# 1_MCU.net
KiCad netlist of a schematic drawn in Altium Designer
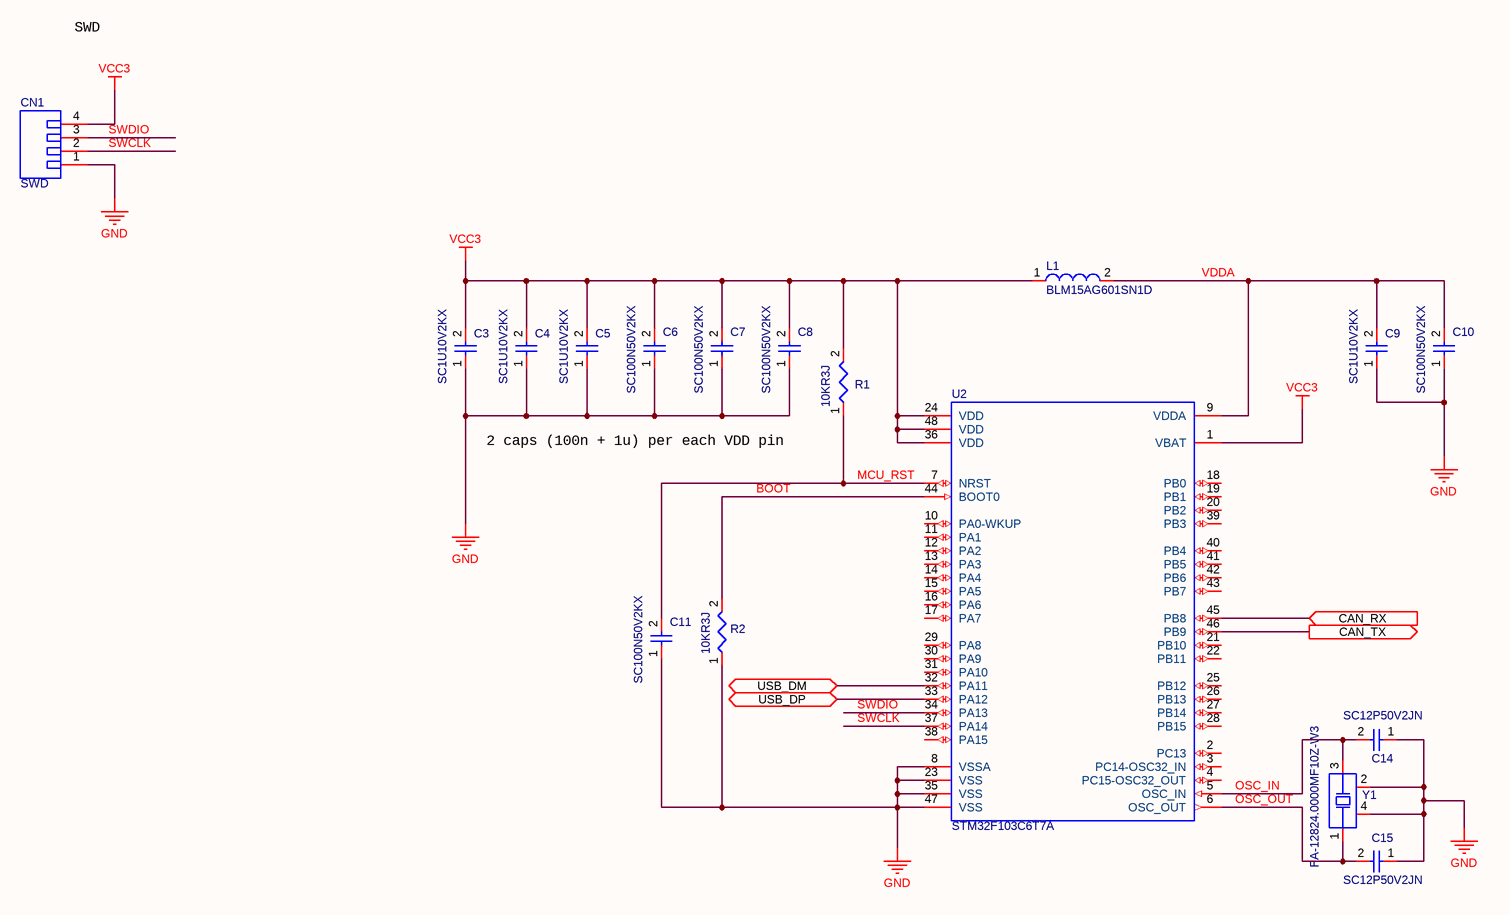
[diagram p0: 1_MCU.SchDoc]

(export (version "E")
  (design (tool "Eeschema 10.0.6"))
  (components
    (comp (ref "C3")
      (value "SC1U10V2KX")
      (footprint "CAPC0402(1005)60_L")
      (description "CAP 1uF 10V ±10% 0402 (1005 Metric) Thickness 0.6mm SMD")
      (libsource (lib "PUMAlib") (part "CAP(0402)1UF10V"))
    )
    (comp (ref "C4")
      (value "SC1U10V2KX")
      (footprint "CAPC0402(1005)60_L")
      (description "CAP 1uF 10V ±10% 0402 (1005 Metric) Thickness 0.6mm SMD")
      (libsource (lib "PUMAlib") (part "CAP(0402)1UF10V"))
    )
    (comp (ref "C5")
      (value "SC1U10V2KX")
      (footprint "CAPC0402(1005)60_L")
      (description "CAP 1uF 10V ±10% 0402 (1005 Metric) Thickness 0.6mm SMD")
      (libsource (lib "PUMAlib") (part "CAP(0402)1UF10V"))
    )
    (comp (ref "C6")
      (value "SC100N50V2KX")
      (footprint "CAPC0402(1005)60_L")
      (description "CAP 100nF 50V ±10% 0402 (1005 Metric) Thickness 0.6mm SMD")
      (libsource (lib "PUMAlib") (part "CAP(0402)100nF50V"))
    )
    (comp (ref "C7")
      (value "SC100N50V2KX")
      (footprint "CAPC0402(1005)60_L")
      (description "CAP 100nF 50V ±10% 0402 (1005 Metric) Thickness 0.6mm SMD")
      (libsource (lib "PUMAlib") (part "CAP(0402)100nF50V"))
    )
    (comp (ref "C8")
      (value "SC100N50V2KX")
      (footprint "CAPC0402(1005)60_L")
      (description "CAP 100nF 50V ±10% 0402 (1005 Metric) Thickness 0.6mm SMD")
      (libsource (lib "PUMAlib") (part "CAP(0402)100nF50V"))
    )
    (comp (ref "C9")
      (value "SC1U10V2KX")
      (footprint "CAPC0402(1005)60_L")
      (description "CAP 1uF 10V ±10% 0402 (1005 Metric) Thickness 0.6mm SMD")
      (libsource (lib "PUMAlib") (part "CAP(0402)1UF10V"))
    )
    (comp (ref "C10")
      (value "SC100N50V2KX")
      (footprint "CAPC0402(1005)60_L")
      (description "CAP 100nF 50V ±10% 0402 (1005 Metric) Thickness 0.6mm SMD")
      (libsource (lib "PUMAlib") (part "CAP(0402)100nF50V"))
    )
    (comp (ref "C11")
      (value "SC100N50V2KX")
      (footprint "CAPC0402(1005)60_L")
      (description "CAP 100nF 50V ±10% 0402 (1005 Metric) Thickness 0.6mm SMD")
      (libsource (lib "PUMAlib") (part "CAP(0402)100nF50V"))
    )
    (comp (ref "C14")
      (value "SC12P50V2JN")
      (footprint "CAPC0402(1005)33_L")
      (description "CAP 12pF 50V ±5% 0402 (1005 Metric) Thickness 0.33mm SMD")
      (libsource (lib "PUMAlib") (part "CAP12pF"))
    )
    (comp (ref "C15")
      (value "SC12P50V2JN")
      (footprint "CAPC0402(1005)33_L")
      (description "CAP 12pF 50V ±5% 0402 (1005 Metric) Thickness 0.33mm SMD")
      (libsource (lib "PUMAlib") (part "CAP12pF"))
    )
    (comp (ref "CN1")
      (value "SWD")
      (footprint "4PHEADERS-2D54")
      (description "4 holes for 18awg wire")
      (fields (field (name "MANUFACTURER") "JST"))
      (libsource (lib "PUMAlib") (part "4PIN-CN"))
    )
    (comp (ref "L1")
      (value "BLM15AG601SN1D")
      (footprint "INDC1005X06L")
      (description "Chip Ferrite Bead Single Type 600 Ohms 300mA")
      (libsource (lib "PUMAlib") (part "IND-filt"))
    )
    (comp (ref "R1")
      (value "10KR3J")
      (footprint "RESC0603(1608)_L")
      (description "10K 0.1W 5% 0603 (1608 Metric)  SMD")
      (libsource (lib "PUMAlib") (part "RES0(0603)_10K"))
    )
    (comp (ref "R2")
      (value "10KR3J")
      (footprint "RESC0603(1608)_L")
      (description "10K 0.1W 5% 0603 (1608 Metric)  SMD")
      (libsource (lib "PUMAlib") (part "RES0(0603)_10K"))
    )
    (comp (ref "U2")
      (value "STM32F103C6T7A")
      (footprint "TSQFP50P900X900X160-48L")
      (description "ARM® Cortex®-M3 STM32F1 Microcontroller IC 32-Bit 72MHz 32KB 48-LFQP (7x7)")
      (libsource (lib "PUMAlib") (part "STM32F103C6T7A"))
    )
    (comp (ref "Y1")
      (value "FA-12824.0000MF10Z-W3")
      (footprint "QRTZ-12mhz")
      (description "Crystal, 24 MHz, +/- 10 ppm, -20 to 75 degC, 4-Pin SMD, RoHS, Tape and Reel")
      (fields (field (name "TOLERANCE") "10ppm"))
      (libsource (lib "PUMAlib") (part "XTAL-1-3-4"))
    )
  )
  (nets
    (net (code "1") (name "/BOOT") (class "Default")
      (node (ref "R2") (pin "2") (pinfunction "2_2") (pintype "passive"))
      (node (ref "U2") (pin "44") (pinfunction "BOOT0_44") (pintype "input"))
    )
    (net (code "2") (name "/CAN_RX") (class "Default")
      (node (ref "U2") (pin "45") (pinfunction "PB8_45") (pintype "bidirectional"))
    )
    (net (code "3") (name "/CAN_TX") (class "Default")
      (node (ref "U2") (pin "46") (pinfunction "PB9_46") (pintype "bidirectional"))
    )
    (net (code "4") (name "/MCU_RST") (class "Default")
      (node (ref "C11") (pin "2") (pinfunction "2_2") (pintype "passive"))
      (node (ref "R1") (pin "1") (pinfunction "1_1") (pintype "passive"))
      (node (ref "U2") (pin "7") (pinfunction "NRST_7") (pintype "bidirectional"))
    )
    (net (code "5") (name "/OSC_IN") (class "Default")
      (node (ref "C14") (pin "2") (pinfunction "2_2") (pintype "passive"))
      (node (ref "U2") (pin "5") (pinfunction "OSC_IN_5") (pintype "input"))
      (node (ref "Y1") (pin "3") (pinfunction "X2_3") (pintype "passive"))
    )
    (net (code "6") (name "/OSC_OUT") (class "Default")
      (node (ref "C15") (pin "2") (pinfunction "2_2") (pintype "passive"))
      (node (ref "U2") (pin "6") (pinfunction "OSC_OUT_6") (pintype "output"))
      (node (ref "Y1") (pin "1") (pinfunction "X1_1") (pintype "passive"))
    )
    (net (code "7") (name "/SWCLK") (class "Default")
      (node (ref "CN1") (pin "2") (pinfunction "2_2") (pintype "passive"))
      (node (ref "U2") (pin "37") (pinfunction "PA14_37") (pintype "bidirectional"))
    )
    (net (code "8") (name "/SWDIO") (class "Default")
      (node (ref "CN1") (pin "3") (pinfunction "3_3") (pintype "passive"))
      (node (ref "U2") (pin "34") (pinfunction "PA13_34") (pintype "bidirectional"))
    )
    (net (code "9") (name "/USB_DM") (class "Default")
      (node (ref "U2") (pin "32") (pinfunction "PA11_32") (pintype "bidirectional"))
    )
    (net (code "10") (name "/USB_DP") (class "Default")
      (node (ref "U2") (pin "33") (pinfunction "PA12_33") (pintype "bidirectional"))
    )
    (net (code "11") (name "/VDDA") (class "Default")
      (node (ref "C10") (pin "2") (pinfunction "2_2") (pintype "passive"))
      (node (ref "C9") (pin "2") (pinfunction "2_2") (pintype "passive"))
      (node (ref "L1") (pin "2") (pinfunction "2_2") (pintype "passive"))
      (node (ref "U2") (pin "9") (pinfunction "VDDA_9") (pintype "power_in"))
    )
    (net (code "12") (name "GND") (class "Default")
      (node (ref "C10") (pin "1") (pinfunction "1_1") (pintype "passive"))
      (node (ref "C11") (pin "1") (pinfunction "1_1") (pintype "passive"))
      (node (ref "C14") (pin "1") (pinfunction "1_1") (pintype "passive"))
      (node (ref "C15") (pin "1") (pinfunction "1_1") (pintype "passive"))
      (node (ref "C3") (pin "1") (pinfunction "1_1") (pintype "passive"))
      (node (ref "C4") (pin "1") (pinfunction "1_1") (pintype "passive"))
      (node (ref "C5") (pin "1") (pinfunction "1_1") (pintype "passive"))
      (node (ref "C6") (pin "1") (pinfunction "1_1") (pintype "passive"))
      (node (ref "C7") (pin "1") (pinfunction "1_1") (pintype "passive"))
      (node (ref "C8") (pin "1") (pinfunction "1_1") (pintype "passive"))
      (node (ref "C9") (pin "1") (pinfunction "1_1") (pintype "passive"))
      (node (ref "CN1") (pin "1") (pinfunction "1_1") (pintype "passive"))
      (node (ref "R2") (pin "1") (pinfunction "1_1") (pintype "passive"))
      (node (ref "U2") (pin "23") (pinfunction "VSS_23") (pintype "power_in"))
      (node (ref "U2") (pin "35") (pinfunction "VSS_35") (pintype "power_in"))
      (node (ref "U2") (pin "47") (pinfunction "VSS_47") (pintype "power_in"))
      (node (ref "U2") (pin "8") (pinfunction "VSSA_8") (pintype "power_in"))
      (node (ref "Y1") (pin "2") (pinfunction "NC_2") (pintype "power_in"))
      (node (ref "Y1") (pin "4") (pinfunction "NC_4") (pintype "power_in"))
    )
    (net (code "13") (name "VCC3") (class "Default")
      (node (ref "C3") (pin "2") (pinfunction "2_2") (pintype "passive"))
      (node (ref "C4") (pin "2") (pinfunction "2_2") (pintype "passive"))
      (node (ref "C5") (pin "2") (pinfunction "2_2") (pintype "passive"))
      (node (ref "C6") (pin "2") (pinfunction "2_2") (pintype "passive"))
      (node (ref "C7") (pin "2") (pinfunction "2_2") (pintype "passive"))
      (node (ref "C8") (pin "2") (pinfunction "2_2") (pintype "passive"))
      (node (ref "CN1") (pin "4") (pinfunction "4_4") (pintype "passive"))
      (node (ref "L1") (pin "1") (pinfunction "1_1") (pintype "passive"))
      (node (ref "R1") (pin "2") (pinfunction "2_2") (pintype "passive"))
      (node (ref "U2") (pin "1") (pinfunction "VBAT_1") (pintype "power_in"))
      (node (ref "U2") (pin "24") (pinfunction "VDD_24") (pintype "power_in"))
      (node (ref "U2") (pin "36") (pinfunction "VDD_36") (pintype "power_in"))
      (node (ref "U2") (pin "48") (pinfunction "VDD_48") (pintype "power_in"))
    )
    (net (code "14") (name "unconnected-(U2-PA0-WKUP-Pad10)") (class "Default")
      (node (ref "U2") (pin "10") (pinfunction "PA0-WKUP_10") (pintype "bidirectional"))
    )
    (net (code "15") (name "unconnected-(U2-PA1-Pad11)") (class "Default")
      (node (ref "U2") (pin "11") (pinfunction "PA1_11") (pintype "bidirectional"))
    )
    (net (code "16") (name "unconnected-(U2-PA2-Pad12)") (class "Default")
      (node (ref "U2") (pin "12") (pinfunction "PA2_12") (pintype "bidirectional"))
    )
    (net (code "17") (name "unconnected-(U2-PA3-Pad13)") (class "Default")
      (node (ref "U2") (pin "13") (pinfunction "PA3_13") (pintype "bidirectional"))
    )
    (net (code "18") (name "unconnected-(U2-PA4-Pad14)") (class "Default")
      (node (ref "U2") (pin "14") (pinfunction "PA4_14") (pintype "bidirectional"))
    )
    (net (code "19") (name "unconnected-(U2-PA5-Pad15)") (class "Default")
      (node (ref "U2") (pin "15") (pinfunction "PA5_15") (pintype "bidirectional"))
    )
    (net (code "20") (name "unconnected-(U2-PA6-Pad16)") (class "Default")
      (node (ref "U2") (pin "16") (pinfunction "PA6_16") (pintype "bidirectional"))
    )
    (net (code "21") (name "unconnected-(U2-PA7-Pad17)") (class "Default")
      (node (ref "U2") (pin "17") (pinfunction "PA7_17") (pintype "bidirectional"))
    )
    (net (code "22") (name "unconnected-(U2-PA8-Pad29)") (class "Default")
      (node (ref "U2") (pin "29") (pinfunction "PA8_29") (pintype "bidirectional"))
    )
    (net (code "23") (name "unconnected-(U2-PA9-Pad30)") (class "Default")
      (node (ref "U2") (pin "30") (pinfunction "PA9_30") (pintype "bidirectional"))
    )
    (net (code "24") (name "unconnected-(U2-PA10-Pad31)") (class "Default")
      (node (ref "U2") (pin "31") (pinfunction "PA10_31") (pintype "bidirectional"))
    )
    (net (code "25") (name "unconnected-(U2-PA15-Pad38)") (class "Default")
      (node (ref "U2") (pin "38") (pinfunction "PA15_38") (pintype "bidirectional"))
    )
    (net (code "26") (name "unconnected-(U2-PB0-Pad18)") (class "Default")
      (node (ref "U2") (pin "18") (pinfunction "PB0_18") (pintype "bidirectional"))
    )
    (net (code "27") (name "unconnected-(U2-PB1-Pad19)") (class "Default")
      (node (ref "U2") (pin "19") (pinfunction "PB1_19") (pintype "bidirectional"))
    )
    (net (code "28") (name "unconnected-(U2-PB2-Pad20)") (class "Default")
      (node (ref "U2") (pin "20") (pinfunction "PB2_20") (pintype "bidirectional"))
    )
    (net (code "29") (name "unconnected-(U2-PB3-Pad39)") (class "Default")
      (node (ref "U2") (pin "39") (pinfunction "PB3_39") (pintype "bidirectional"))
    )
    (net (code "30") (name "unconnected-(U2-PB4-Pad40)") (class "Default")
      (node (ref "U2") (pin "40") (pinfunction "PB4_40") (pintype "bidirectional"))
    )
    (net (code "31") (name "unconnected-(U2-PB5-Pad41)") (class "Default")
      (node (ref "U2") (pin "41") (pinfunction "PB5_41") (pintype "bidirectional"))
    )
    (net (code "32") (name "unconnected-(U2-PB6-Pad42)") (class "Default")
      (node (ref "U2") (pin "42") (pinfunction "PB6_42") (pintype "bidirectional"))
    )
    (net (code "33") (name "unconnected-(U2-PB7-Pad43)") (class "Default")
      (node (ref "U2") (pin "43") (pinfunction "PB7_43") (pintype "bidirectional"))
    )
    (net (code "34") (name "unconnected-(U2-PB10-Pad21)") (class "Default")
      (node (ref "U2") (pin "21") (pinfunction "PB10_21") (pintype "bidirectional"))
    )
    (net (code "35") (name "unconnected-(U2-PB11-Pad22)") (class "Default")
      (node (ref "U2") (pin "22") (pinfunction "PB11_22") (pintype "bidirectional"))
    )
    (net (code "36") (name "unconnected-(U2-PB12-Pad25)") (class "Default")
      (node (ref "U2") (pin "25") (pinfunction "PB12_25") (pintype "bidirectional"))
    )
    (net (code "37") (name "unconnected-(U2-PB13-Pad26)") (class "Default")
      (node (ref "U2") (pin "26") (pinfunction "PB13_26") (pintype "bidirectional"))
    )
    (net (code "38") (name "unconnected-(U2-PB14-Pad27)") (class "Default")
      (node (ref "U2") (pin "27") (pinfunction "PB14_27") (pintype "bidirectional"))
    )
    (net (code "39") (name "unconnected-(U2-PB15-Pad28)") (class "Default")
      (node (ref "U2") (pin "28") (pinfunction "PB15_28") (pintype "bidirectional"))
    )
    (net (code "40") (name "unconnected-(U2-PC13-Pad2)") (class "Default")
      (node (ref "U2") (pin "2") (pinfunction "PC13_2") (pintype "bidirectional"))
    )
    (net (code "41") (name "unconnected-(U2-PC14-OSC32_IN-Pad3)") (class "Default")
      (node (ref "U2") (pin "3") (pinfunction "PC14-OSC32_IN_3") (pintype "bidirectional"))
    )
    (net (code "42") (name "unconnected-(U2-PC15-OSC32_OUT-Pad4)") (class "Default")
      (node (ref "U2") (pin "4") (pinfunction "PC15-OSC32_OUT_4") (pintype "bidirectional"))
    )
  )
)
